# controller.net
KiCad netlist of a schematic drawn in EAGLE
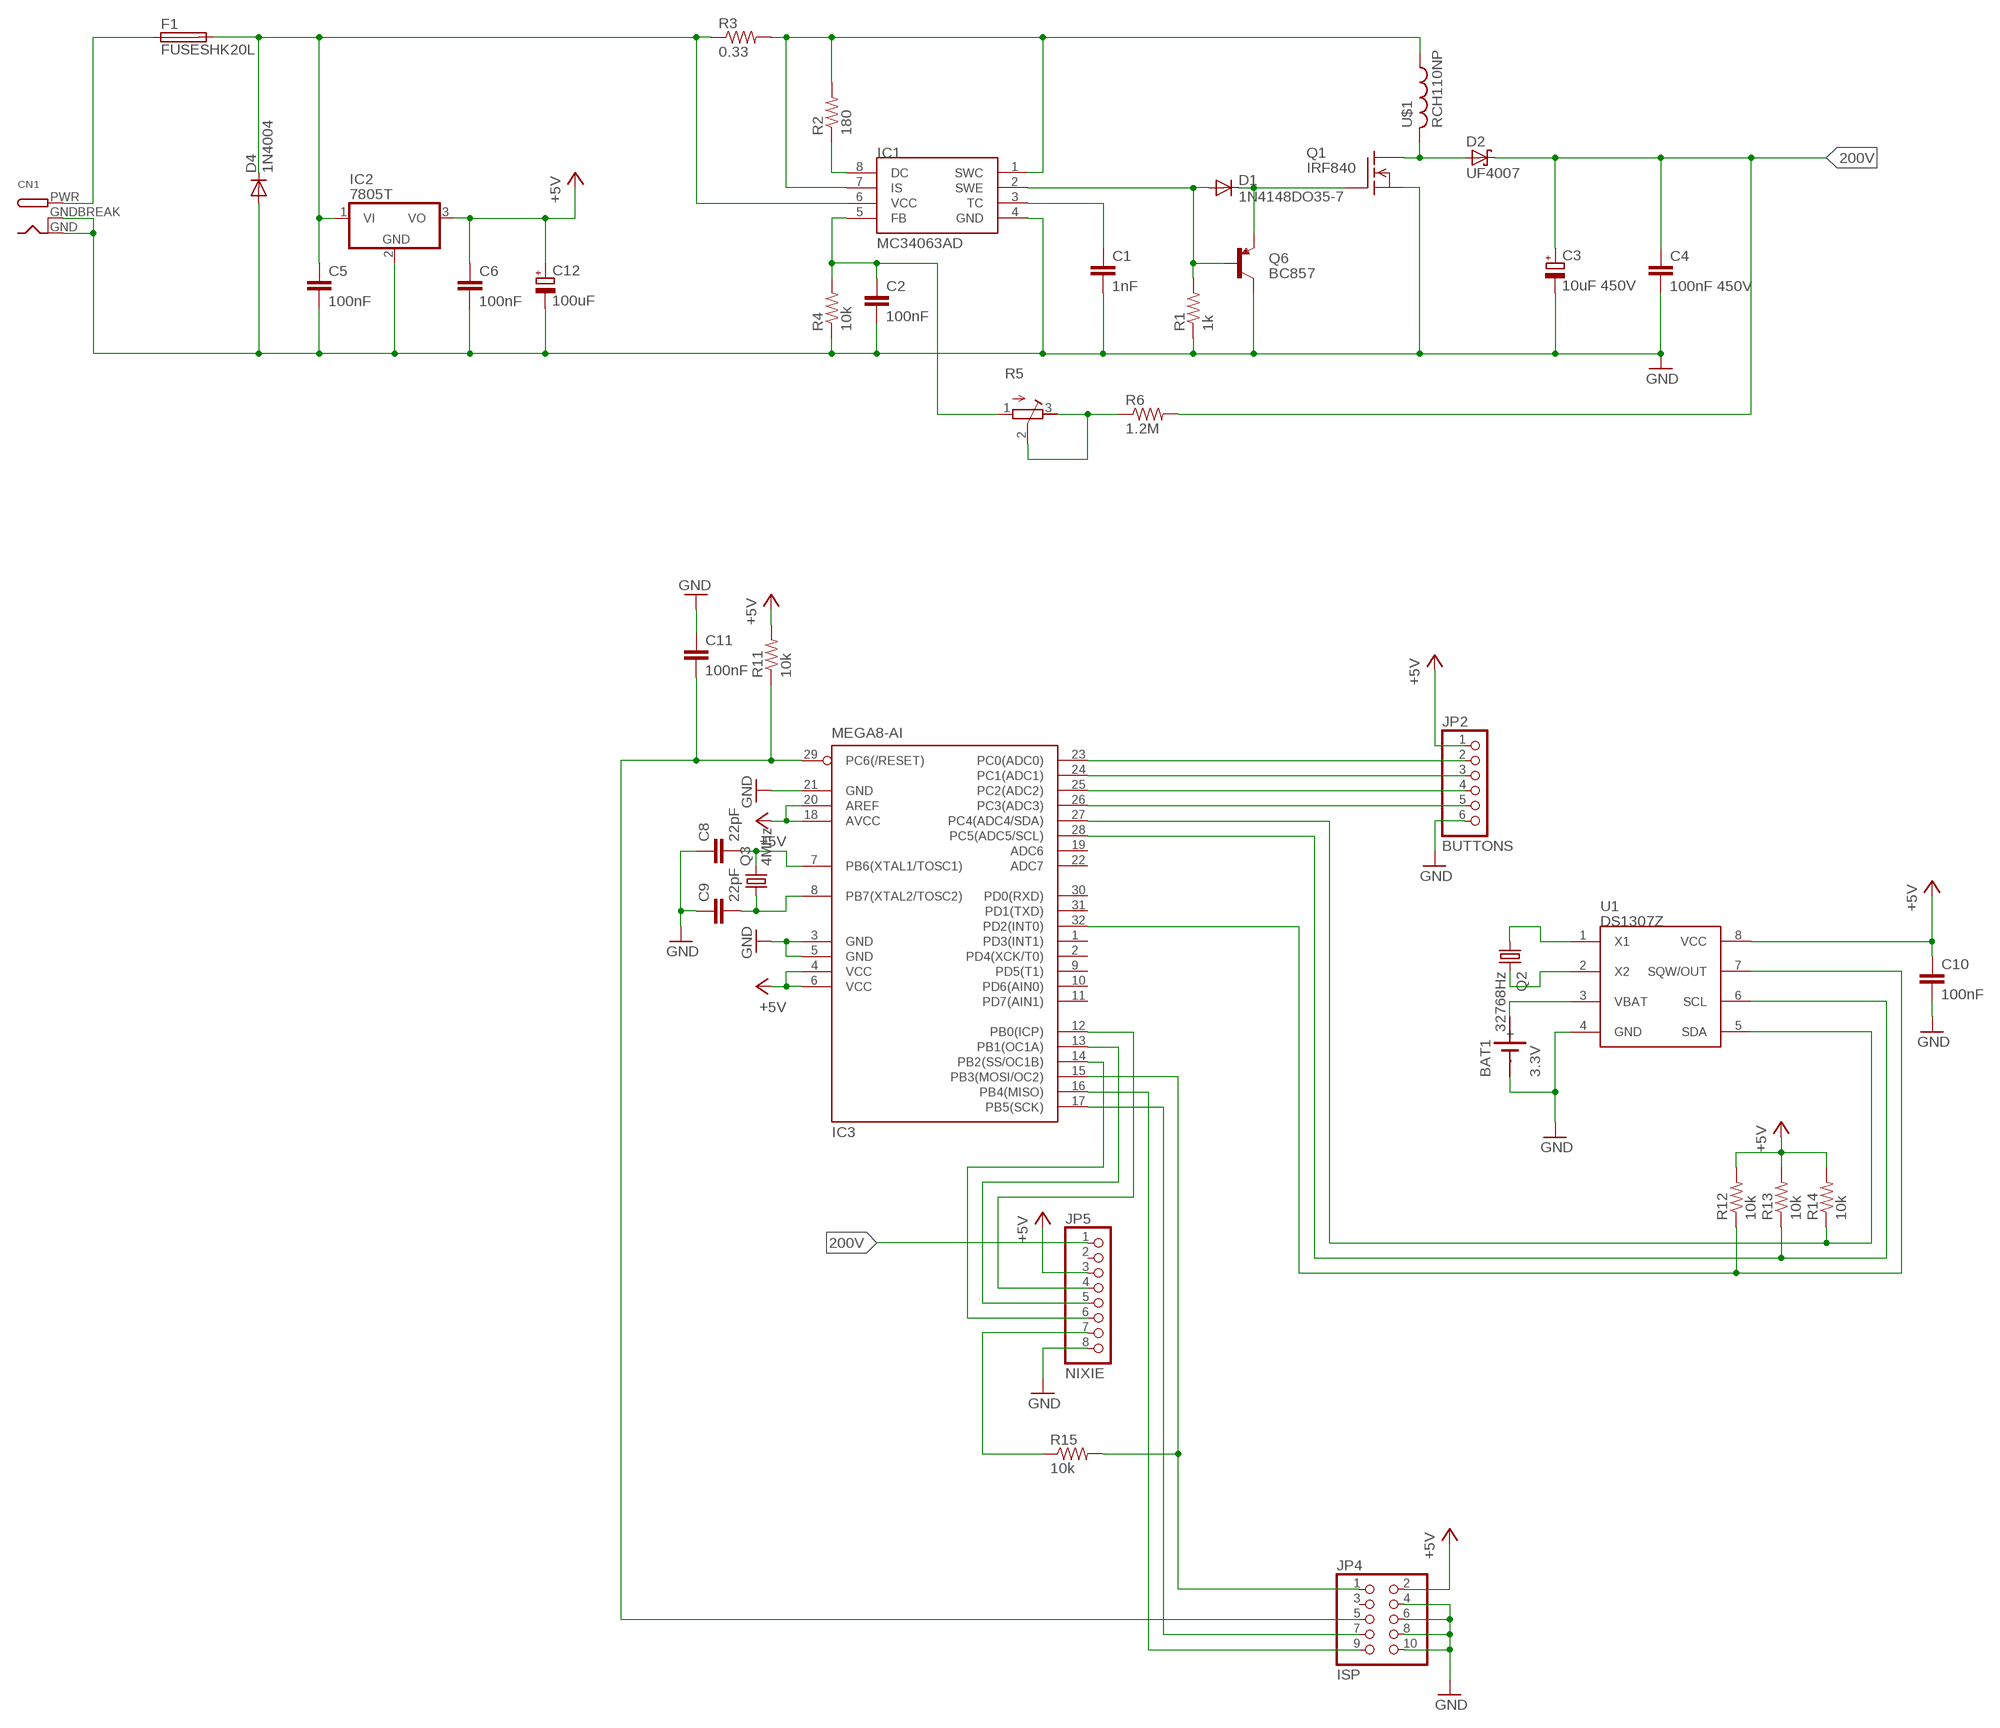
[diagram p0: schematic, sheet 1]

(export (version "E")
  (design (tool "Eeschema 10.0.6"))
  (components
    (comp (ref "BAT1")
      (value "3.3V")
      (footprint "eagle-import:SN2032")
      (libsource (lib "eagle-import") (part "SN2032"))
    )
    (comp (ref "C1")
      (value "1nF")
      (footprint "eagle-import:0805")
      (libsource (lib "eagle-import") (part "CAP0805"))
    )
    (comp (ref "C2")
      (value "100nF")
      (footprint "eagle-import:0805")
      (libsource (lib "eagle-import") (part "CAP0805"))
    )
    (comp (ref "C3")
      (value "10uF 450V")
      (footprint "eagle-import:E5-13")
      (libsource (lib "eagle-import") (part "resistor_CPOL-EUE5-13"))
    )
    (comp (ref "C4")
      (value "100nF 450V")
      (footprint "eagle-import:CAP-PTH-LARGE")
      (libsource (lib "eagle-import") (part "CAPPTH3"))
    )
    (comp (ref "C5")
      (value "100nF")
      (footprint "eagle-import:0805")
      (libsource (lib "eagle-import") (part "CAP0805"))
    )
    (comp (ref "C6")
      (value "100nF")
      (footprint "eagle-import:0805")
      (libsource (lib "eagle-import") (part "CAP0805"))
    )
    (comp (ref "C8")
      (value "22pF")
      (footprint "eagle-import:0805")
      (libsource (lib "eagle-import") (part "CAP0805"))
    )
    (comp (ref "C9")
      (value "22pF")
      (footprint "eagle-import:0805")
      (libsource (lib "eagle-import") (part "CAP0805"))
    )
    (comp (ref "C10")
      (value "100nF")
      (footprint "eagle-import:0805")
      (libsource (lib "eagle-import") (part "CAP0805"))
    )
    (comp (ref "C11")
      (value "100nF")
      (footprint "eagle-import:0805")
      (libsource (lib "eagle-import") (part "CAP0805"))
    )
    (comp (ref "C12")
      (value "100uF")
      (footprint "eagle-import:E3,5-8")
      (libsource (lib "eagle-import") (part "CPOL-EUE3.5-8"))
    )
    (comp (ref "CN1")
      (value "DCBARRELPTH")
      (footprint "eagle-import:DCJACK_2MM_PTH")
      (libsource (lib "eagle-import") (part "DCBARRELPTH"))
    )
    (comp (ref "D1")
      (value "1N4148DO35-7")
      (footprint "eagle-import:DO35-7")
      (libsource (lib "eagle-import") (part "1N4148DO35-7"))
    )
    (comp (ref "D2")
      (value "UF4007")
      (footprint "eagle-import:DO41-7.6")
      (libsource (lib "eagle-import") (part "1N5817-B"))
    )
    (comp (ref "D4")
      (value "1N4004")
      (footprint "eagle-import:DO41-10")
      (libsource (lib "eagle-import") (part "1N4004"))
    )
    (comp (ref "F1")
      (value "FUSESHK20L")
      (footprint "eagle-import:SHK20L")
      (libsource (lib "eagle-import") (part "FUSESHK20L"))
    )
    (comp (ref "IC1")
      (value "MC34063AD")
      (footprint "eagle-import:SOIC8")
      (libsource (lib "eagle-import") (part "MC34063AD"))
    )
    (comp (ref "IC2")
      (value "7805T")
      (footprint "eagle-import:TO220H")
      (libsource (lib "eagle-import") (part "78T05"))
    )
    (comp (ref "IC3")
      (value "MEGA8-AI")
      (footprint "eagle-import:TQFP32-08")
      (fields (field (name "MPN") "ATMEGA8-16AU"))
      (libsource (lib "eagle-import") (part "MEGA8-AI"))
    )
    (comp (ref "JP2")
      (value "BUTTONS")
      (footprint "eagle-import:1X06_90")
      (libsource (lib "eagle-import") (part "PINHD-1X6/90"))
    )
    (comp (ref "JP4")
      (value "ISP")
      (footprint "eagle-import:2X05_90")
      (libsource (lib "eagle-import") (part "PINHD-2X5/90"))
    )
    (comp (ref "JP5")
      (value "NIXIE")
      (footprint "eagle-import:1X08")
      (libsource (lib "eagle-import") (part "PINHD-1X8"))
    )
    (comp (ref "Q1")
      (value "IRF840")
      (footprint "eagle-import:TO220")
      (libsource (lib "eagle-import") (part "IRF840"))
    )
    (comp (ref "Q2")
      (value "32768Hz")
      (footprint "eagle-import:TC38H")
      (libsource (lib "eagle-import") (part "CRYSTALTC38H"))
    )
    (comp (ref "Q3")
      (value "4MHz")
      (footprint "eagle-import:HC49U-V")
      (libsource (lib "eagle-import") (part "CRYSTALHC49U-V"))
    )
    (comp (ref "Q6")
      (value "BC857")
      (footprint "eagle-import:SOT23-3")
      (libsource (lib "eagle-import") (part "TRANSISTOR_PNPSMD"))
    )
    (comp (ref "R1")
      (value "1k")
      (footprint "eagle-import:0805")
      (libsource (lib "eagle-import") (part "RESISTOR0805-RES"))
    )
    (comp (ref "R2")
      (value "180")
      (footprint "eagle-import:0805")
      (libsource (lib "eagle-import") (part "RESISTOR0805-RES"))
    )
    (comp (ref "R3")
      (value "0.33")
      (footprint "eagle-import:AXIAL-0.8")
      (libsource (lib "eagle-import") (part "RESISTORPTH-2W"))
    )
    (comp (ref "R4")
      (value "10k")
      (footprint "eagle-import:0805")
      (libsource (lib "eagle-import") (part "RESISTOR0805-RES"))
    )
    (comp (ref "R5")
      (value "R-TRIMM64Z")
      (footprint "eagle-import:RTRIM64Z")
      (libsource (lib "eagle-import") (part "R-TRIMM64Z"))
    )
    (comp (ref "R6")
      (value "1.2M")
      (footprint "eagle-import:AXIAL-0.8")
      (libsource (lib "eagle-import") (part "RESISTORPTH-2W"))
    )
    (comp (ref "R11")
      (value "10k")
      (footprint "eagle-import:0805")
      (libsource (lib "eagle-import") (part "RESISTOR0805-RES"))
    )
    (comp (ref "R12")
      (value "10k")
      (footprint "eagle-import:0805")
      (libsource (lib "eagle-import") (part "RESISTOR0805-RES"))
    )
    (comp (ref "R13")
      (value "10k")
      (footprint "eagle-import:0805")
      (libsource (lib "eagle-import") (part "RESISTOR0805-RES"))
    )
    (comp (ref "R14")
      (value "10k")
      (footprint "eagle-import:0805")
      (libsource (lib "eagle-import") (part "RESISTOR0805-RES"))
    )
    (comp (ref "R15")
      (value "10k")
      (footprint "eagle-import:0805")
      (libsource (lib "eagle-import") (part "RESISTOR0805-RES"))
    )
    (comp (ref "U$1")
      (value "RCH110NP")
      (footprint "eagle-import:RCH110NP")
      (libsource (lib "eagle-import") (part "RCH110NP"))
    )
    (comp (ref "U1")
      (value "DS1307Z")
      (footprint "eagle-import:SOIC8")
      (libsource (lib "eagle-import") (part "DS1307Z"))
    )
  )
  (nets
    (net (code "1") (name "+5V") (class "Default")
      (node (ref "C10") (pin "1") (pinfunction "1_1") (pintype "passive"))
      (node (ref "C12") (pin "+") (pinfunction "+_+") (pintype "passive"))
      (node (ref "C6") (pin "1") (pinfunction "1_1") (pintype "passive"))
      (node (ref "IC2") (pin "3") (pinfunction "VO_3") (pintype "passive"))
      (node (ref "IC3") (pin "18") (pinfunction "AVCC_18") (pintype "power_in"))
      (node (ref "IC3") (pin "20") (pinfunction "AREF_20") (pintype "passive"))
      (node (ref "IC3") (pin "4") (pinfunction "VCC_4") (pintype "power_in"))
      (node (ref "IC3") (pin "6") (pinfunction "VCC_6") (pintype "power_in"))
      (node (ref "JP2") (pin "1") (pinfunction "1_1") (pintype "passive"))
      (node (ref "JP4") (pin "2") (pinfunction "2_2") (pintype "passive"))
      (node (ref "JP5") (pin "3") (pinfunction "3_3") (pintype "passive"))
      (node (ref "R11") (pin "2") (pinfunction "2_2") (pintype "passive"))
      (node (ref "R12") (pin "2") (pinfunction "2_2") (pintype "passive"))
      (node (ref "R13") (pin "2") (pinfunction "2_2") (pintype "passive"))
      (node (ref "R14") (pin "2") (pinfunction "2_2") (pintype "passive"))
      (node (ref "U1") (pin "8") (pinfunction "VCC_8") (pintype "power_in"))
    )
    (net (code "2") (name "200V") (class "Default")
      (node (ref "C3") (pin "+") (pinfunction "+_+") (pintype "passive"))
      (node (ref "C4") (pin "1") (pinfunction "1_1") (pintype "passive"))
      (node (ref "D2") (pin "C") (pinfunction "C_C") (pintype "passive"))
      (node (ref "JP5") (pin "1") (pinfunction "1_1") (pintype "passive"))
      (node (ref "R6") (pin "P$2") (pinfunction "2_P$2") (pintype "passive"))
    )
    (net (code "3") (name "GND") (class "Default")
      (node (ref "BAT1") (pin "-") (pinfunction "-_-") (pintype "passive"))
      (node (ref "C1") (pin "2") (pinfunction "2_2") (pintype "passive"))
      (node (ref "C10") (pin "2") (pinfunction "2_2") (pintype "passive"))
      (node (ref "C11") (pin "1") (pinfunction "1_1") (pintype "passive"))
      (node (ref "C12") (pin "-") (pinfunction "-_-") (pintype "passive"))
      (node (ref "C2") (pin "2") (pinfunction "2_2") (pintype "passive"))
      (node (ref "C3") (pin "-") (pinfunction "-_-") (pintype "passive"))
      (node (ref "C4") (pin "2") (pinfunction "2_2") (pintype "passive"))
      (node (ref "C5") (pin "2") (pinfunction "2_2") (pintype "passive"))
      (node (ref "C6") (pin "2") (pinfunction "2_2") (pintype "passive"))
      (node (ref "C8") (pin "1") (pinfunction "1_1") (pintype "passive"))
      (node (ref "C9") (pin "1") (pinfunction "1_1") (pintype "passive"))
      (node (ref "CN1") (pin "GND") (pinfunction "GND_GND") (pintype "power_in"))
      (node (ref "CN1") (pin "GNDBREAK") (pinfunction "GNDBREAK_GNDBREAK") (pintype "power_in"))
      (node (ref "D4") (pin "A") (pinfunction "A_A") (pintype "passive"))
      (node (ref "IC1") (pin "4") (pinfunction "GND_4") (pintype "passive"))
      (node (ref "IC2") (pin "2") (pinfunction "GND_2") (pintype "passive"))
      (node (ref "IC3") (pin "21") (pinfunction "GND_21") (pintype "power_in"))
      (node (ref "IC3") (pin "3") (pinfunction "GND_3") (pintype "power_in"))
      (node (ref "IC3") (pin "5") (pinfunction "GND_5") (pintype "power_in"))
      (node (ref "JP2") (pin "6") (pinfunction "6_6") (pintype "passive"))
      (node (ref "JP4") (pin "10") (pinfunction "10_10") (pintype "passive"))
      (node (ref "JP4") (pin "4") (pinfunction "4_4") (pintype "passive"))
      (node (ref "JP4") (pin "6") (pinfunction "6_6") (pintype "passive"))
      (node (ref "JP4") (pin "8") (pinfunction "8_8") (pintype "passive"))
      (node (ref "JP5") (pin "8") (pinfunction "8_8") (pintype "passive"))
      (node (ref "Q1") (pin "3") (pinfunction "S_3") (pintype "passive"))
      (node (ref "Q6") (pin "3") (pinfunction "C_3") (pintype "passive"))
      (node (ref "R1") (pin "1") (pinfunction "1_1") (pintype "passive"))
      (node (ref "R4") (pin "1") (pinfunction "1_1") (pintype "passive"))
      (node (ref "U1") (pin "4") (pinfunction "GND_4") (pintype "power_in"))
    )
    (net (code "4") (name "Net-(F1-1)") (class "Default")
      (node (ref "CN1") (pin "PWR") (pinfunction "PWR_PWR") (pintype "power_in"))
      (node (ref "F1") (pin "1A") (pinfunction "1_1A") (pintype "passive"))
    )
    (net (code "5") (name "Net-(F1-2)") (class "Default")
      (node (ref "C5") (pin "1") (pinfunction "1_1") (pintype "passive"))
      (node (ref "D4") (pin "C") (pinfunction "C_C") (pintype "passive"))
      (node (ref "F1") (pin "2A") (pinfunction "2_2A") (pintype "passive"))
      (node (ref "IC1") (pin "6") (pinfunction "VCC_6") (pintype "passive"))
      (node (ref "IC2") (pin "1") (pinfunction "VI_1") (pintype "input"))
      (node (ref "R3") (pin "P$1") (pinfunction "1_P$1") (pintype "passive"))
    )
    (net (code "6") (name "Net-(IC1-DC)") (class "Default")
      (node (ref "IC1") (pin "8") (pinfunction "DC_8") (pintype "passive"))
      (node (ref "R2") (pin "1") (pinfunction "1_1") (pintype "passive"))
    )
    (net (code "7") (name "Net-(IC1-FB)") (class "Default")
      (node (ref "C2") (pin "1") (pinfunction "1_1") (pintype "passive"))
      (node (ref "IC1") (pin "5") (pinfunction "FB_5") (pintype "passive"))
      (node (ref "R4") (pin "2") (pinfunction "2_2") (pintype "passive"))
      (node (ref "R5") (pin "1") (pinfunction "A_1") (pintype "passive"))
    )
    (net (code "8") (name "Net-(IC1-IS)") (class "Default")
      (node (ref "IC1") (pin "1") (pinfunction "SWC_1") (pintype "passive"))
      (node (ref "IC1") (pin "7") (pinfunction "IS_7") (pintype "passive"))
      (node (ref "R2") (pin "2") (pinfunction "2_2") (pintype "passive"))
      (node (ref "R3") (pin "P$2") (pinfunction "2_P$2") (pintype "passive"))
      (node (ref "U$1") (pin "A") (pinfunction "1_A") (pintype "passive"))
    )
    (net (code "9") (name "Net-(IC1-SWE)") (class "Default")
      (node (ref "D1") (pin "A") (pinfunction "A_A") (pintype "passive"))
      (node (ref "IC1") (pin "2") (pinfunction "SWE_2") (pintype "passive"))
      (node (ref "Q6") (pin "1") (pinfunction "B_1") (pintype "passive"))
      (node (ref "R1") (pin "2") (pinfunction "2_2") (pintype "passive"))
    )
    (net (code "10") (name "Net-(IC1-TC)") (class "Default")
      (node (ref "C1") (pin "1") (pinfunction "1_1") (pintype "passive"))
      (node (ref "IC1") (pin "3") (pinfunction "TC_3") (pintype "passive"))
    )
    (net (code "11") (name "Net-(IC3-PB0(ICP))") (class "Default")
      (node (ref "IC3") (pin "12") (pinfunction "PB0(ICP)_12") (pintype "bidirectional"))
      (node (ref "JP5") (pin "4") (pinfunction "4_4") (pintype "passive"))
    )
    (net (code "12") (name "Net-(IC3-PB1(OC1A))") (class "Default")
      (node (ref "IC3") (pin "13") (pinfunction "PB1(OC1A)_13") (pintype "bidirectional"))
      (node (ref "JP5") (pin "5") (pinfunction "5_5") (pintype "passive"))
    )
    (net (code "13") (name "Net-(IC3-PB2(SS{slash}OC1B))") (class "Default")
      (node (ref "IC3") (pin "14") (pinfunction "PB2(SS/OC1B)_14") (pintype "bidirectional"))
      (node (ref "JP5") (pin "6") (pinfunction "6_6") (pintype "passive"))
    )
    (net (code "14") (name "Net-(IC3-PB3(MOSI{slash}OC2))") (class "Default")
      (node (ref "IC3") (pin "15") (pinfunction "PB3(MOSI/OC2)_15") (pintype "bidirectional"))
      (node (ref "JP4") (pin "1") (pinfunction "1_1") (pintype "passive"))
      (node (ref "R15") (pin "2") (pinfunction "2_2") (pintype "passive"))
    )
    (net (code "15") (name "Net-(IC3-PB4(MISO))") (class "Default")
      (node (ref "IC3") (pin "16") (pinfunction "PB4(MISO)_16") (pintype "bidirectional"))
      (node (ref "JP4") (pin "9") (pinfunction "9_9") (pintype "passive"))
    )
    (net (code "16") (name "Net-(IC3-PB5(SCK))") (class "Default")
      (node (ref "IC3") (pin "17") (pinfunction "PB5(SCK)_17") (pintype "bidirectional"))
      (node (ref "JP4") (pin "7") (pinfunction "7_7") (pintype "passive"))
    )
    (net (code "17") (name "Net-(IC3-PB6(XTAL1{slash}TOSC1))") (class "Default")
      (node (ref "C8") (pin "2") (pinfunction "2_2") (pintype "passive"))
      (node (ref "IC3") (pin "7") (pinfunction "PB6(XTAL1/TOSC1)_7") (pintype "bidirectional"))
      (node (ref "Q3") (pin "2") (pinfunction "2_2") (pintype "passive"))
    )
    (net (code "18") (name "Net-(IC3-PB7(XTAL2{slash}TOSC2))") (class "Default")
      (node (ref "C9") (pin "2") (pinfunction "2_2") (pintype "passive"))
      (node (ref "IC3") (pin "8") (pinfunction "PB7(XTAL2/TOSC2)_8") (pintype "bidirectional"))
      (node (ref "Q3") (pin "1") (pinfunction "1_1") (pintype "passive"))
    )
    (net (code "19") (name "Net-(IC3-PC0(ADC0))") (class "Default")
      (node (ref "IC3") (pin "23") (pinfunction "PC0(ADC0)_23") (pintype "bidirectional"))
      (node (ref "JP2") (pin "2") (pinfunction "2_2") (pintype "passive"))
    )
    (net (code "20") (name "Net-(IC3-PC1(ADC1))") (class "Default")
      (node (ref "IC3") (pin "24") (pinfunction "PC1(ADC1)_24") (pintype "bidirectional"))
      (node (ref "JP2") (pin "3") (pinfunction "3_3") (pintype "passive"))
    )
    (net (code "21") (name "Net-(IC3-PC2(ADC2))") (class "Default")
      (node (ref "IC3") (pin "25") (pinfunction "PC2(ADC2)_25") (pintype "bidirectional"))
      (node (ref "JP2") (pin "4") (pinfunction "4_4") (pintype "passive"))
    )
    (net (code "22") (name "Net-(IC3-PC3(ADC3))") (class "Default")
      (node (ref "IC3") (pin "26") (pinfunction "PC3(ADC3)_26") (pintype "bidirectional"))
      (node (ref "JP2") (pin "5") (pinfunction "5_5") (pintype "passive"))
    )
    (net (code "23") (name "Net-(IC3-PC4(ADC4{slash}SDA))") (class "Default")
      (node (ref "IC3") (pin "27") (pinfunction "PC4(ADC4/SDA)_27") (pintype "bidirectional"))
      (node (ref "R14") (pin "1") (pinfunction "1_1") (pintype "passive"))
      (node (ref "U1") (pin "5") (pinfunction "SDA_5") (pintype "bidirectional"))
    )
    (net (code "24") (name "Net-(IC3-PC5(ADC5{slash}SCL))") (class "Default")
      (node (ref "IC3") (pin "28") (pinfunction "PC5(ADC5/SCL)_28") (pintype "bidirectional"))
      (node (ref "R13") (pin "1") (pinfunction "1_1") (pintype "passive"))
      (node (ref "U1") (pin "6") (pinfunction "SCL_6") (pintype "bidirectional"))
    )
    (net (code "25") (name "Net-(IC3-PC6({slash}RESET))") (class "Default")
      (node (ref "C11") (pin "2") (pinfunction "2_2") (pintype "passive"))
      (node (ref "IC3") (pin "29") (pinfunction "PC6(/RESET)_29") (pintype "bidirectional"))
      (node (ref "JP4") (pin "5") (pinfunction "5_5") (pintype "passive"))
      (node (ref "R11") (pin "1") (pinfunction "1_1") (pintype "passive"))
    )
    (net (code "26") (name "Net-(IC3-PD2(INT0))") (class "Default")
      (node (ref "IC3") (pin "32") (pinfunction "PD2(INT0)_32") (pintype "bidirectional"))
      (node (ref "R12") (pin "1") (pinfunction "1_1") (pintype "passive"))
      (node (ref "U1") (pin "7") (pinfunction "SQW/OUT_7") (pintype "output"))
    )
    (net (code "27") (name "Net-(JP5-Pad7)") (class "Default")
      (node (ref "JP5") (pin "7") (pinfunction "7_7") (pintype "passive"))
      (node (ref "R15") (pin "1") (pinfunction "1_1") (pintype "passive"))
    )
    (net (code "28") (name "Net-(Q1-D)") (class "Default")
      (node (ref "D2") (pin "A") (pinfunction "A_A") (pintype "passive"))
      (node (ref "Q1") (pin "2") (pinfunction "D_2") (pintype "passive"))
      (node (ref "U$1") (pin "B") (pinfunction "2_B") (pintype "passive"))
    )
    (net (code "29") (name "Net-(Q1-G)") (class "Default")
      (node (ref "D1") (pin "C") (pinfunction "C_C") (pintype "passive"))
      (node (ref "Q1") (pin "1") (pinfunction "G_1") (pintype "passive"))
      (node (ref "Q6") (pin "2") (pinfunction "E_2") (pintype "passive"))
    )
    (net (code "30") (name "Net-(R5-E)") (class "Default")
      (node (ref "R5") (pin "2") (pinfunction "S_2") (pintype "passive"))
      (node (ref "R5") (pin "3") (pinfunction "E_3") (pintype "passive"))
      (node (ref "R6") (pin "P$1") (pinfunction "1_P$1") (pintype "passive"))
    )
    (net (code "31") (name "Net-(U1-VBAT)") (class "Default")
      (node (ref "BAT1") (pin "+") (pinfunction "+_+") (pintype "passive"))
      (node (ref "U1") (pin "3") (pinfunction "VBAT_3") (pintype "power_in"))
    )
    (net (code "32") (name "Net-(U1-X1)") (class "Default")
      (node (ref "Q2") (pin "1") (pinfunction "1_1") (pintype "passive"))
      (node (ref "U1") (pin "1") (pinfunction "X1_1") (pintype "bidirectional"))
    )
    (net (code "33") (name "Net-(U1-X2)") (class "Default")
      (node (ref "Q2") (pin "2") (pinfunction "2_2") (pintype "passive"))
      (node (ref "U1") (pin "2") (pinfunction "X2_2") (pintype "bidirectional"))
    )
    (net (code "34") (name "unconnected-(IC3-ADC6-Pad19)") (class "Default")
      (node (ref "IC3") (pin "19") (pinfunction "ADC6_19") (pintype "bidirectional"))
    )
    (net (code "35") (name "unconnected-(IC3-ADC7-Pad22)") (class "Default")
      (node (ref "IC3") (pin "22") (pinfunction "ADC7_22") (pintype "bidirectional"))
    )
    (net (code "36") (name "unconnected-(IC3-PD0(RXD)-Pad30)") (class "Default")
      (node (ref "IC3") (pin "30") (pinfunction "PD0(RXD)_30") (pintype "bidirectional"))
    )
    (net (code "37") (name "unconnected-(IC3-PD1(TXD)-Pad31)") (class "Default")
      (node (ref "IC3") (pin "31") (pinfunction "PD1(TXD)_31") (pintype "bidirectional"))
    )
    (net (code "38") (name "unconnected-(IC3-PD3(INT1)-Pad1)") (class "Default")
      (node (ref "IC3") (pin "1") (pinfunction "PD3(INT1)_1") (pintype "bidirectional"))
    )
    (net (code "39") (name "unconnected-(IC3-PD4(XCK{slash}T0)-Pad2)") (class "Default")
      (node (ref "IC3") (pin "2") (pinfunction "PD4(XCK/T0)_2") (pintype "bidirectional"))
    )
    (net (code "40") (name "unconnected-(IC3-PD5(T1)-Pad9)") (class "Default")
      (node (ref "IC3") (pin "9") (pinfunction "PD5(T1)_9") (pintype "bidirectional"))
    )
    (net (code "41") (name "unconnected-(IC3-PD6(AIN0)-Pad10)") (class "Default")
      (node (ref "IC3") (pin "10") (pinfunction "PD6(AIN0)_10") (pintype "bidirectional"))
    )
    (net (code "42") (name "unconnected-(IC3-PD7(AIN1)-Pad11)") (class "Default")
      (node (ref "IC3") (pin "11") (pinfunction "PD7(AIN1)_11") (pintype "bidirectional"))
    )
    (net (code "43") (name "unconnected-(JP4-Pad3)") (class "Default")
      (node (ref "JP4") (pin "3") (pinfunction "3_3") (pintype "passive"))
    )
    (net (code "44") (name "unconnected-(JP5-Pad2)") (class "Default")
      (node (ref "JP5") (pin "2") (pinfunction "2_2") (pintype "passive"))
    )
  )
)
